# wemos_gpio_7x.net
KiCad netlist of a schematic drawn in EAGLE
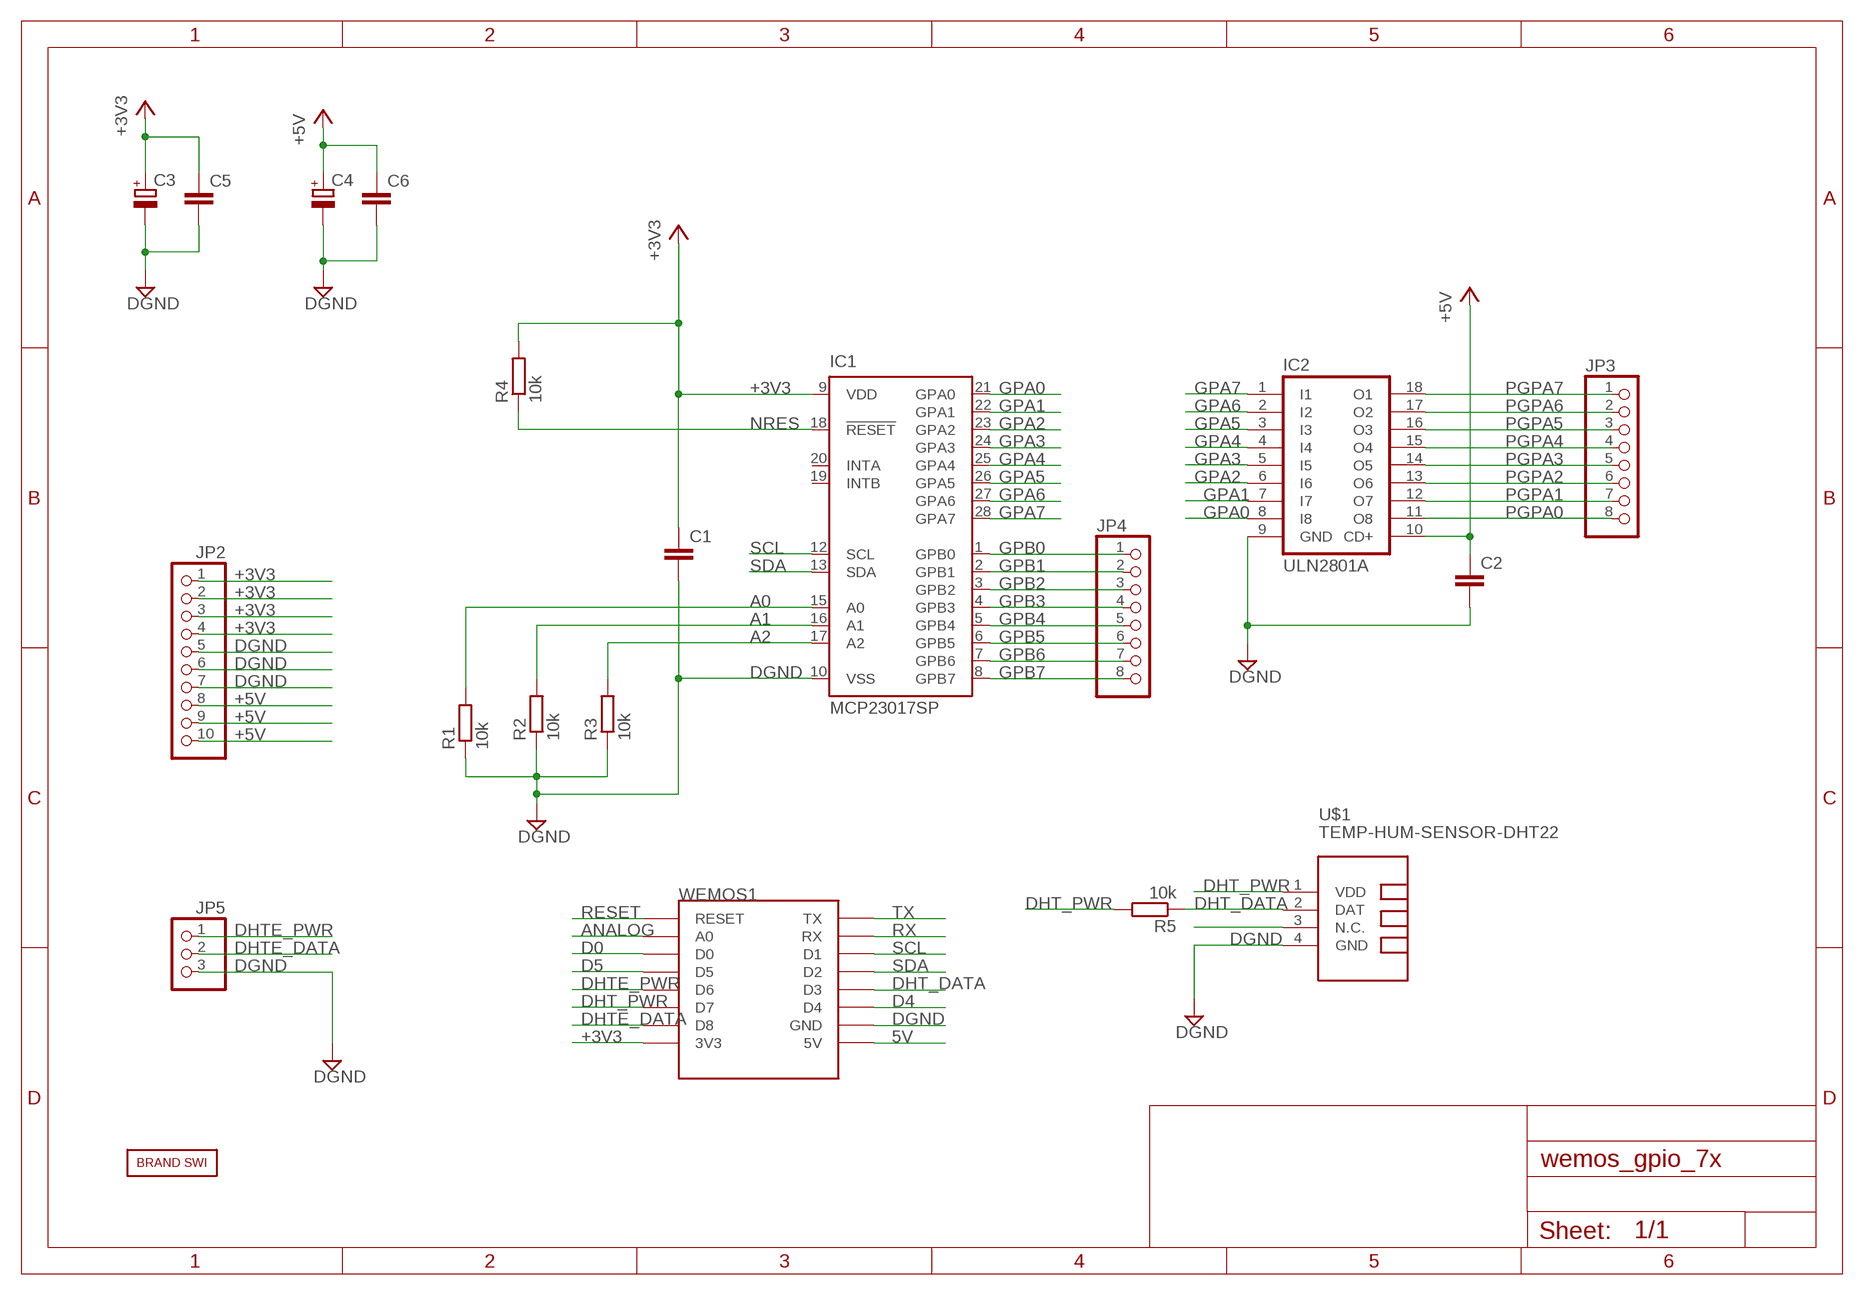
[diagram p0: schematic, sheet 1]

(export (version "E")
  (design (tool "Eeschema 10.0.6"))
  (components
    (comp (ref "C1")
      (value "C-EUC1210")
      (footprint "eagle-import:C1210")
      (libsource (lib "eagle-import") (part "C-EUC1210"))
    )
    (comp (ref "C2")
      (value "C-EUC1210")
      (footprint "eagle-import:C1210")
      (libsource (lib "eagle-import") (part "C-EUC1210"))
    )
    (comp (ref "C3")
      (value "CPOL-EUTT5D7")
      (footprint "eagle-import:TT5D7")
      (libsource (lib "eagle-import") (part "CPOL-EUTT5D7"))
    )
    (comp (ref "C4")
      (value "CPOL-EUTT5D7")
      (footprint "eagle-import:TT5D7")
      (libsource (lib "eagle-import") (part "CPOL-EUTT5D7"))
    )
    (comp (ref "C5")
      (value "C-EUC1210")
      (footprint "eagle-import:C1210")
      (libsource (lib "eagle-import") (part "C-EUC1210"))
    )
    (comp (ref "C6")
      (value "C-EUC1210")
      (footprint "eagle-import:C1210")
      (libsource (lib "eagle-import") (part "C-EUC1210"))
    )
    (comp (ref "IC1")
      (value "MCP23017SP")
      (footprint "eagle-import:DIL28-3")
      (fields (field (name "MF") "MICROCHIP") (field (name "MPN") "MCP23017-E/SP"))
      (libsource (lib "eagle-import") (part "MCP23017SP"))
    )
    (comp (ref "IC2")
      (value "ULN2801A")
      (footprint "eagle-import:DIL18")
      (libsource (lib "eagle-import") (part "ULN2801A"))
    )
    (comp (ref "JP2")
      (value "PINHD-1X10")
      (footprint "eagle-import:1X10")
      (libsource (lib "eagle-import") (part "PINHD-1X10"))
    )
    (comp (ref "JP3")
      (value "PINHD-1X8")
      (footprint "eagle-import:1X08")
      (libsource (lib "eagle-import") (part "PINHD-1X8"))
    )
    (comp (ref "JP4")
      (value "PINHD-1X8")
      (footprint "eagle-import:1X08")
      (libsource (lib "eagle-import") (part "PINHD-1X8"))
    )
    (comp (ref "JP5")
      (value "PINHD-1X3")
      (footprint "eagle-import:1X03")
      (libsource (lib "eagle-import") (part "PINHD-1X3"))
    )
    (comp (ref "R1")
      (value "10k")
      (footprint "eagle-import:M1206")
      (libsource (lib "eagle-import") (part "R-EU_M1206"))
    )
    (comp (ref "R2")
      (value "10k")
      (footprint "eagle-import:M1206")
      (libsource (lib "eagle-import") (part "R-EU_M1206"))
    )
    (comp (ref "R3")
      (value "10k")
      (footprint "eagle-import:M1206")
      (libsource (lib "eagle-import") (part "R-EU_M1206"))
    )
    (comp (ref "R4")
      (value "10k")
      (footprint "eagle-import:M1206")
      (libsource (lib "eagle-import") (part "R-EU_M1206"))
    )
    (comp (ref "R5")
      (value "10k")
      (footprint "eagle-import:M1206")
      (libsource (lib "eagle-import") (part "R-EU_M1206"))
    )
    (comp (ref "U$1")
      (value "TEMP-HUM-SENSOR-DHT22")
      (footprint "eagle-import:TEMP-HUM-SENSOR-DHT22")
      (libsource (lib "eagle-import") (part "TEMP-HUM-SENSOR-DHT22"))
    )
    (comp (ref "U$2")
      (value "BRAND_SWI5X7")
      (footprint "eagle-import:BRAND_SWI_5X7")
      (libsource (lib "eagle-import") (part "BRAND_SWI5X7"))
    )
    (comp (ref "WEMOS1")
      (value "WEMOS-D1-MINI")
      (footprint "eagle-import:WEMOS-D1-MINI")
      (libsource (lib "eagle-import") (part "WEMOS-D1-MINI"))
    )
  )
  (nets
    (net (code "1") (name "+3V3") (class "Default")
      (node (ref "C1") (pin "1") (pinfunction "1_1") (pintype "passive"))
      (node (ref "C3") (pin "+") (pinfunction "+_+") (pintype "passive"))
      (node (ref "C5") (pin "1") (pinfunction "1_1") (pintype "passive"))
      (node (ref "IC1") (pin "9") (pinfunction "VDD_9") (pintype "power_in"))
      (node (ref "JP2") (pin "1") (pinfunction "1_1") (pintype "passive"))
      (node (ref "JP2") (pin "2") (pinfunction "2_2") (pintype "passive"))
      (node (ref "JP2") (pin "3") (pinfunction "3_3") (pintype "passive"))
      (node (ref "JP2") (pin "4") (pinfunction "4_4") (pintype "passive"))
      (node (ref "R4") (pin "2") (pinfunction "2_2") (pintype "passive"))
      (node (ref "WEMOS1") (pin "3V3") (pinfunction "3V3_3V3") (pintype "bidirectional"))
    )
    (net (code "2") (name "+5V") (class "Default")
      (node (ref "C2") (pin "1") (pinfunction "1_1") (pintype "passive"))
      (node (ref "C4") (pin "+") (pinfunction "+_+") (pintype "passive"))
      (node (ref "C6") (pin "1") (pinfunction "1_1") (pintype "passive"))
      (node (ref "IC2") (pin "10") (pinfunction "CD+_10") (pintype "passive"))
      (node (ref "JP2") (pin "10") (pinfunction "10_10") (pintype "passive"))
      (node (ref "JP2") (pin "8") (pinfunction "8_8") (pintype "passive"))
      (node (ref "JP2") (pin "9") (pinfunction "9_9") (pintype "passive"))
    )
    (net (code "3") (name "/5V") (class "Default")
      (node (ref "WEMOS1") (pin "5V") (pinfunction "5V_5V") (pintype "bidirectional"))
    )
    (net (code "4") (name "/A0") (class "Default")
      (node (ref "IC1") (pin "15") (pinfunction "A0_15") (pintype "input"))
      (node (ref "R1") (pin "2") (pinfunction "2_2") (pintype "passive"))
    )
    (net (code "5") (name "/A1") (class "Default")
      (node (ref "IC1") (pin "16") (pinfunction "A1_16") (pintype "input"))
      (node (ref "R2") (pin "2") (pinfunction "2_2") (pintype "passive"))
    )
    (net (code "6") (name "/A2") (class "Default")
      (node (ref "IC1") (pin "17") (pinfunction "A2_17") (pintype "input"))
      (node (ref "R3") (pin "2") (pinfunction "2_2") (pintype "passive"))
    )
    (net (code "7") (name "/ANALOG") (class "Default")
      (node (ref "WEMOS1") (pin "A0") (pinfunction "A0_A0") (pintype "bidirectional"))
    )
    (net (code "8") (name "/D0") (class "Default")
      (node (ref "WEMOS1") (pin "D0") (pinfunction "D0_D0") (pintype "bidirectional"))
    )
    (net (code "9") (name "/D4") (class "Default")
      (node (ref "WEMOS1") (pin "D4") (pinfunction "D4_D4") (pintype "bidirectional"))
    )
    (net (code "10") (name "/D5") (class "Default")
      (node (ref "WEMOS1") (pin "D5") (pinfunction "D5_D5") (pintype "bidirectional"))
    )
    (net (code "11") (name "/DHTE_DATA") (class "Default")
      (node (ref "JP5") (pin "2") (pinfunction "2_2") (pintype "passive"))
      (node (ref "WEMOS1") (pin "D8") (pinfunction "D8_D8") (pintype "bidirectional"))
    )
    (net (code "12") (name "/DHTE_PWR") (class "Default")
      (node (ref "JP5") (pin "1") (pinfunction "1_1") (pintype "passive"))
      (node (ref "WEMOS1") (pin "D6") (pinfunction "D6_D6") (pintype "bidirectional"))
    )
    (net (code "13") (name "/DHT_DATA") (class "Default")
      (node (ref "R5") (pin "1") (pinfunction "1_1") (pintype "passive"))
      (node (ref "U$1") (pin "2") (pinfunction "DAT_2") (pintype "bidirectional"))
      (node (ref "WEMOS1") (pin "D3") (pinfunction "D3_D3") (pintype "bidirectional"))
    )
    (net (code "14") (name "/DHT_PWR") (class "Default")
      (node (ref "R5") (pin "2") (pinfunction "2_2") (pintype "passive"))
      (node (ref "U$1") (pin "1") (pinfunction "VDD_1") (pintype "power_in"))
      (node (ref "WEMOS1") (pin "D7") (pinfunction "D7_D7") (pintype "bidirectional"))
    )
    (net (code "15") (name "/GPA0") (class "Default")
      (node (ref "IC1") (pin "21") (pinfunction "GPA0_21") (pintype "bidirectional"))
      (node (ref "IC2") (pin "8") (pinfunction "I8_8") (pintype "input"))
    )
    (net (code "16") (name "/GPA1") (class "Default")
      (node (ref "IC1") (pin "22") (pinfunction "GPA1_22") (pintype "bidirectional"))
      (node (ref "IC2") (pin "7") (pinfunction "I7_7") (pintype "input"))
    )
    (net (code "17") (name "/GPA2") (class "Default")
      (node (ref "IC1") (pin "23") (pinfunction "GPA2_23") (pintype "bidirectional"))
      (node (ref "IC2") (pin "6") (pinfunction "I6_6") (pintype "input"))
    )
    (net (code "18") (name "/GPA3") (class "Default")
      (node (ref "IC1") (pin "24") (pinfunction "GPA3_24") (pintype "bidirectional"))
      (node (ref "IC2") (pin "5") (pinfunction "I5_5") (pintype "input"))
    )
    (net (code "19") (name "/GPA4") (class "Default")
      (node (ref "IC1") (pin "25") (pinfunction "GPA4_25") (pintype "bidirectional"))
      (node (ref "IC2") (pin "4") (pinfunction "I4_4") (pintype "input"))
    )
    (net (code "20") (name "/GPA5") (class "Default")
      (node (ref "IC1") (pin "26") (pinfunction "GPA5_26") (pintype "bidirectional"))
      (node (ref "IC2") (pin "3") (pinfunction "I3_3") (pintype "input"))
    )
    (net (code "21") (name "/GPA6") (class "Default")
      (node (ref "IC1") (pin "27") (pinfunction "GPA6_27") (pintype "bidirectional"))
      (node (ref "IC2") (pin "2") (pinfunction "I2_2") (pintype "input"))
    )
    (net (code "22") (name "/GPA7") (class "Default")
      (node (ref "IC1") (pin "28") (pinfunction "GPA7_28") (pintype "bidirectional"))
      (node (ref "IC2") (pin "1") (pinfunction "I1_1") (pintype "input"))
    )
    (net (code "23") (name "/GPB0") (class "Default")
      (node (ref "IC1") (pin "1") (pinfunction "GPB0_1") (pintype "bidirectional"))
      (node (ref "JP4") (pin "1") (pinfunction "1_1") (pintype "passive"))
    )
    (net (code "24") (name "/GPB1") (class "Default")
      (node (ref "IC1") (pin "2") (pinfunction "GPB1_2") (pintype "bidirectional"))
      (node (ref "JP4") (pin "2") (pinfunction "2_2") (pintype "passive"))
    )
    (net (code "25") (name "/GPB2") (class "Default")
      (node (ref "IC1") (pin "3") (pinfunction "GPB2_3") (pintype "bidirectional"))
      (node (ref "JP4") (pin "3") (pinfunction "3_3") (pintype "passive"))
    )
    (net (code "26") (name "/GPB3") (class "Default")
      (node (ref "IC1") (pin "4") (pinfunction "GPB3_4") (pintype "bidirectional"))
      (node (ref "JP4") (pin "4") (pinfunction "4_4") (pintype "passive"))
    )
    (net (code "27") (name "/GPB4") (class "Default")
      (node (ref "IC1") (pin "5") (pinfunction "GPB4_5") (pintype "bidirectional"))
      (node (ref "JP4") (pin "5") (pinfunction "5_5") (pintype "passive"))
    )
    (net (code "28") (name "/GPB5") (class "Default")
      (node (ref "IC1") (pin "6") (pinfunction "GPB5_6") (pintype "bidirectional"))
      (node (ref "JP4") (pin "6") (pinfunction "6_6") (pintype "passive"))
    )
    (net (code "29") (name "/GPB6") (class "Default")
      (node (ref "IC1") (pin "7") (pinfunction "GPB6_7") (pintype "bidirectional"))
      (node (ref "JP4") (pin "7") (pinfunction "7_7") (pintype "passive"))
    )
    (net (code "30") (name "/GPB7") (class "Default")
      (node (ref "IC1") (pin "8") (pinfunction "GPB7_8") (pintype "bidirectional"))
      (node (ref "JP4") (pin "8") (pinfunction "8_8") (pintype "passive"))
    )
    (net (code "31") (name "/NRES") (class "Default")
      (node (ref "IC1") (pin "18") (pinfunction "~{RESET}_18") (pintype "input"))
      (node (ref "R4") (pin "1") (pinfunction "1_1") (pintype "passive"))
    )
    (net (code "32") (name "/PGPA0") (class "Default")
      (node (ref "IC2") (pin "11") (pinfunction "O8_11") (pintype "open_collector"))
      (node (ref "JP3") (pin "8") (pinfunction "8_8") (pintype "passive"))
    )
    (net (code "33") (name "/PGPA1") (class "Default")
      (node (ref "IC2") (pin "12") (pinfunction "O7_12") (pintype "open_collector"))
      (node (ref "JP3") (pin "7") (pinfunction "7_7") (pintype "passive"))
    )
    (net (code "34") (name "/PGPA2") (class "Default")
      (node (ref "IC2") (pin "13") (pinfunction "O6_13") (pintype "open_collector"))
      (node (ref "JP3") (pin "6") (pinfunction "6_6") (pintype "passive"))
    )
    (net (code "35") (name "/PGPA3") (class "Default")
      (node (ref "IC2") (pin "14") (pinfunction "O5_14") (pintype "open_collector"))
      (node (ref "JP3") (pin "5") (pinfunction "5_5") (pintype "passive"))
    )
    (net (code "36") (name "/PGPA4") (class "Default")
      (node (ref "IC2") (pin "15") (pinfunction "O4_15") (pintype "open_collector"))
      (node (ref "JP3") (pin "4") (pinfunction "4_4") (pintype "passive"))
    )
    (net (code "37") (name "/PGPA5") (class "Default")
      (node (ref "IC2") (pin "16") (pinfunction "O3_16") (pintype "open_collector"))
      (node (ref "JP3") (pin "3") (pinfunction "3_3") (pintype "passive"))
    )
    (net (code "38") (name "/PGPA6") (class "Default")
      (node (ref "IC2") (pin "17") (pinfunction "O2_17") (pintype "open_collector"))
      (node (ref "JP3") (pin "2") (pinfunction "2_2") (pintype "passive"))
    )
    (net (code "39") (name "/PGPA7") (class "Default")
      (node (ref "IC2") (pin "18") (pinfunction "O1_18") (pintype "open_collector"))
      (node (ref "JP3") (pin "1") (pinfunction "1_1") (pintype "passive"))
    )
    (net (code "40") (name "/RESET") (class "Default")
      (node (ref "WEMOS1") (pin "RESET") (pinfunction "RESET_RESET") (pintype "bidirectional"))
    )
    (net (code "41") (name "/RX") (class "Default")
      (node (ref "WEMOS1") (pin "RX") (pinfunction "RX_RX") (pintype "bidirectional"))
    )
    (net (code "42") (name "/SCL") (class "Default")
      (node (ref "IC1") (pin "12") (pinfunction "SCL_12") (pintype "input"))
      (node (ref "WEMOS1") (pin "D1") (pinfunction "D1_D1") (pintype "bidirectional"))
    )
    (net (code "43") (name "/SDA") (class "Default")
      (node (ref "IC1") (pin "13") (pinfunction "SDA_13") (pintype "bidirectional"))
      (node (ref "WEMOS1") (pin "D2") (pinfunction "D2_D2") (pintype "bidirectional"))
    )
    (net (code "44") (name "/TX") (class "Default")
      (node (ref "WEMOS1") (pin "TX") (pinfunction "TX_TX") (pintype "bidirectional"))
    )
    (net (code "45") (name "DGND") (class "Default")
      (node (ref "C1") (pin "2") (pinfunction "2_2") (pintype "passive"))
      (node (ref "C2") (pin "2") (pinfunction "2_2") (pintype "passive"))
      (node (ref "C3") (pin "-") (pinfunction "-_-") (pintype "passive"))
      (node (ref "C4") (pin "-") (pinfunction "-_-") (pintype "passive"))
      (node (ref "C5") (pin "2") (pinfunction "2_2") (pintype "passive"))
      (node (ref "C6") (pin "2") (pinfunction "2_2") (pintype "passive"))
      (node (ref "IC1") (pin "10") (pinfunction "VSS_10") (pintype "power_in"))
      (node (ref "IC2") (pin "9") (pinfunction "GND_9") (pintype "power_in"))
      (node (ref "JP2") (pin "5") (pinfunction "5_5") (pintype "passive"))
      (node (ref "JP2") (pin "6") (pinfunction "6_6") (pintype "passive"))
      (node (ref "JP2") (pin "7") (pinfunction "7_7") (pintype "passive"))
      (node (ref "JP5") (pin "3") (pinfunction "3_3") (pintype "passive"))
      (node (ref "R1") (pin "1") (pinfunction "1_1") (pintype "passive"))
      (node (ref "R2") (pin "1") (pinfunction "1_1") (pintype "passive"))
      (node (ref "R3") (pin "1") (pinfunction "1_1") (pintype "passive"))
      (node (ref "U$1") (pin "4") (pinfunction "GND_4") (pintype "power_in"))
      (node (ref "WEMOS1") (pin "GND") (pinfunction "GND_GND") (pintype "bidirectional"))
    )
    (net (code "46") (name "unconnected-(IC1-INTA-Pad20)") (class "Default")
      (node (ref "IC1") (pin "20") (pinfunction "INTA_20") (pintype "output"))
    )
    (net (code "47") (name "unconnected-(IC1-INTB-Pad19)") (class "Default")
      (node (ref "IC1") (pin "19") (pinfunction "INTB_19") (pintype "output"))
    )
    (net (code "48") (name "unconnected-(U$1-N.C.-Pad3)") (class "Default")
      (node (ref "U$1") (pin "3") (pinfunction "N.C._3") (pintype "passive"))
    )
  )
)
